# sensor.net
KiCad netlist of a schematic drawn in EAGLE
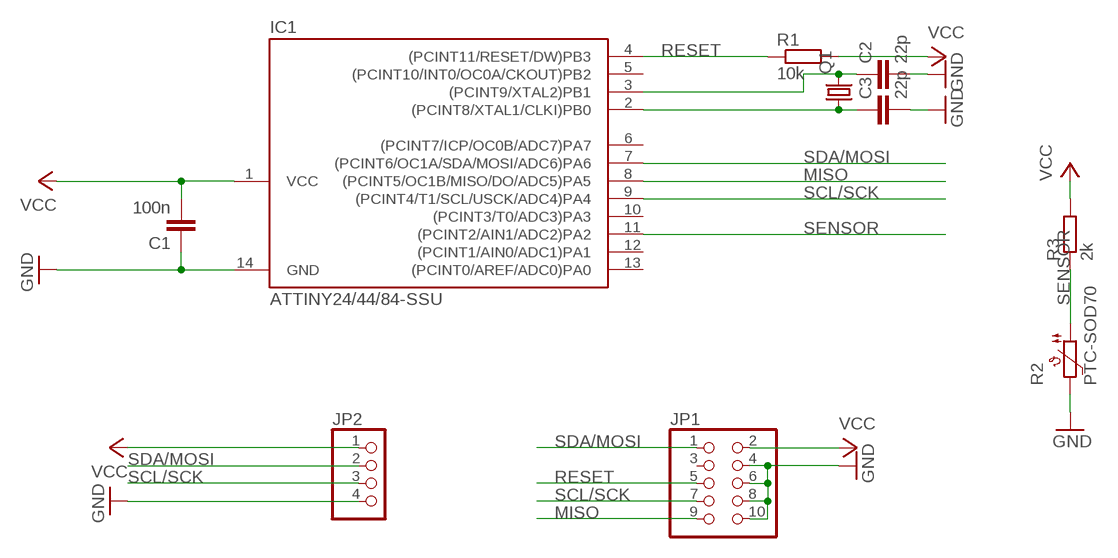
[diagram p0: schematic, sheet 1]

(export (version "E")
  (design (tool "Eeschema 10.0.6"))
  (components
    (comp (ref "C1")
      (value "100n")
      (footprint "eagle-import:C0805")
      (libsource (lib "eagle-import") (part "C-EUC0805"))
    )
    (comp (ref "C2")
      (value "22p")
      (footprint "eagle-import:C0805")
      (libsource (lib "eagle-import") (part "C-EUC0805"))
    )
    (comp (ref "C3")
      (value "22p")
      (footprint "eagle-import:C0805")
      (libsource (lib "eagle-import") (part "C-EUC0805"))
    )
    (comp (ref "IC1")
      (value "ATTINY24/44/84-SSU")
      (footprint "eagle-import:SOIC14")
      (libsource (lib "eagle-import") (part "ATTINY24/44/84-SSU"))
    )
    (comp (ref "JP1")
      (value "PINHD-2X5")
      (footprint "eagle-import:2X05")
      (libsource (lib "eagle-import") (part "PINHD-2X5"))
    )
    (comp (ref "JP2")
      (value "PINHD-1X4")
      (footprint "eagle-import:1X04")
      (libsource (lib "eagle-import") (part "PINHD-1X4"))
    )
    (comp (ref "Q1")
      (value "CRYSTALHC49UP")
      (footprint "eagle-import:HC49UP")
      (libsource (lib "eagle-import") (part "CRYSTALHC49UP"))
    )
    (comp (ref "R1")
      (value "10k")
      (footprint "eagle-import:M0805")
      (libsource (lib "eagle-import") (part "R-EU_M0805"))
    )
    (comp (ref "R2")
      (value "PTC-SOD70")
      (footprint "eagle-import:SOD70")
      (libsource (lib "eagle-import") (part "PTC-SOD70"))
    )
    (comp (ref "R3")
      (value "2k")
      (footprint "eagle-import:M0805")
      (libsource (lib "eagle-import") (part "R-EU_M0805"))
    )
  )
  (nets
    (net (code "1") (name "/MISO") (class "Default")
      (node (ref "IC1") (pin "8") (pinfunction "(PCINT5/OC1B/MISO/DO/ADC5)PA5_8") (pintype "bidirectional"))
      (node (ref "JP1") (pin "9") (pinfunction "9_9") (pintype "passive"))
    )
    (net (code "2") (name "/RESET") (class "Default")
      (node (ref "IC1") (pin "4") (pinfunction "(PCINT11/RESET/DW)PB3_4") (pintype "bidirectional"))
      (node (ref "JP1") (pin "5") (pinfunction "5_5") (pintype "passive"))
      (node (ref "R1") (pin "1") (pinfunction "1_1") (pintype "passive"))
    )
    (net (code "3") (name "/SCL{slash}SCK") (class "Default")
      (node (ref "IC1") (pin "9") (pinfunction "(PCINT4/T1/SCL/USCK/ADC4)PA4_9") (pintype "bidirectional"))
      (node (ref "JP1") (pin "7") (pinfunction "7_7") (pintype "passive"))
      (node (ref "JP2") (pin "3") (pinfunction "3_3") (pintype "passive"))
    )
    (net (code "4") (name "/SDA{slash}MOSI") (class "Default")
      (node (ref "IC1") (pin "7") (pinfunction "(PCINT6/OC1A/SDA/MOSI/ADC6)PA6_7") (pintype "bidirectional"))
      (node (ref "JP1") (pin "1") (pinfunction "1_1") (pintype "passive"))
      (node (ref "JP2") (pin "2") (pinfunction "2_2") (pintype "passive"))
    )
    (net (code "5") (name "/SENSOR") (class "Default")
      (node (ref "IC1") (pin "11") (pinfunction "(PCINT2/AIN1/ADC2)PA2_11") (pintype "bidirectional"))
      (node (ref "R2") (pin "1") (pinfunction "1_1") (pintype "passive"))
      (node (ref "R3") (pin "1") (pinfunction "1_1") (pintype "passive"))
    )
    (net (code "6") (name "GND") (class "Default")
      (node (ref "C1") (pin "1") (pinfunction "1_1") (pintype "passive"))
      (node (ref "C2") (pin "2") (pinfunction "2_2") (pintype "passive"))
      (node (ref "C3") (pin "2") (pinfunction "2_2") (pintype "passive"))
      (node (ref "IC1") (pin "14") (pinfunction "GND_14") (pintype "power_in"))
      (node (ref "JP1") (pin "10") (pinfunction "10_10") (pintype "passive"))
      (node (ref "JP1") (pin "4") (pinfunction "4_4") (pintype "passive"))
      (node (ref "JP1") (pin "6") (pinfunction "6_6") (pintype "passive"))
      (node (ref "JP1") (pin "8") (pinfunction "8_8") (pintype "passive"))
      (node (ref "JP2") (pin "4") (pinfunction "4_4") (pintype "passive"))
      (node (ref "R2") (pin "2") (pinfunction "2_2") (pintype "passive"))
    )
    (net (code "7") (name "Net-(IC1-(PCINT8{slash}XTAL1{slash}CLKI)PB0)") (class "Default")
      (node (ref "C3") (pin "1") (pinfunction "1_1") (pintype "passive"))
      (node (ref "IC1") (pin "2") (pinfunction "(PCINT8/XTAL1/CLKI)PB0_2") (pintype "bidirectional"))
      (node (ref "Q1") (pin "1") (pinfunction "1_1") (pintype "passive"))
    )
    (net (code "8") (name "Net-(IC1-(PCINT9{slash}XTAL2)PB1)") (class "Default")
      (node (ref "C2") (pin "1") (pinfunction "1_1") (pintype "passive"))
      (node (ref "IC1") (pin "3") (pinfunction "(PCINT9/XTAL2)PB1_3") (pintype "bidirectional"))
      (node (ref "Q1") (pin "2") (pinfunction "2_2") (pintype "passive"))
    )
    (net (code "9") (name "VCC") (class "Default")
      (node (ref "C1") (pin "2") (pinfunction "2_2") (pintype "passive"))
      (node (ref "IC1") (pin "1") (pinfunction "VCC_1") (pintype "power_in"))
      (node (ref "JP1") (pin "2") (pinfunction "2_2") (pintype "passive"))
      (node (ref "JP2") (pin "1") (pinfunction "1_1") (pintype "passive"))
      (node (ref "R1") (pin "2") (pinfunction "2_2") (pintype "passive"))
      (node (ref "R3") (pin "2") (pinfunction "2_2") (pintype "passive"))
    )
    (net (code "10") (name "unconnected-(IC1-(PCINT0{slash}AREF{slash}ADC0)PA0-Pad13)") (class "Default")
      (node (ref "IC1") (pin "13") (pinfunction "(PCINT0/AREF/ADC0)PA0_13") (pintype "bidirectional"))
    )
    (net (code "11") (name "unconnected-(IC1-(PCINT1{slash}AIN0{slash}ADC1)PA1-Pad12)") (class "Default")
      (node (ref "IC1") (pin "12") (pinfunction "(PCINT1/AIN0/ADC1)PA1_12") (pintype "bidirectional"))
    )
    (net (code "12") (name "unconnected-(IC1-(PCINT3{slash}T0{slash}ADC3)PA3-Pad10)") (class "Default")
      (node (ref "IC1") (pin "10") (pinfunction "(PCINT3/T0/ADC3)PA3_10") (pintype "bidirectional"))
    )
    (net (code "13") (name "unconnected-(IC1-(PCINT7{slash}ICP{slash}OC0B{slash}ADC7)PA7-Pad6)") (class "Default")
      (node (ref "IC1") (pin "6") (pinfunction "(PCINT7/ICP/OC0B/ADC7)PA7_6") (pintype "bidirectional"))
    )
    (net (code "14") (name "unconnected-(IC1-(PCINT10{slash}INT0{slash}OC0A{slash}CKOUT)PB2-Pad5)") (class "Default")
      (node (ref "IC1") (pin "5") (pinfunction "(PCINT10/INT0/OC0A/CKOUT)PB2_5") (pintype "bidirectional"))
    )
    (net (code "15") (name "unconnected-(JP1-Pad3)") (class "Default")
      (node (ref "JP1") (pin "3") (pinfunction "3_3") (pintype "passive"))
    )
  )
)
